# CH32F203C6T6-R0.net
KiCad netlist of a schematic drawn in Altium Designer
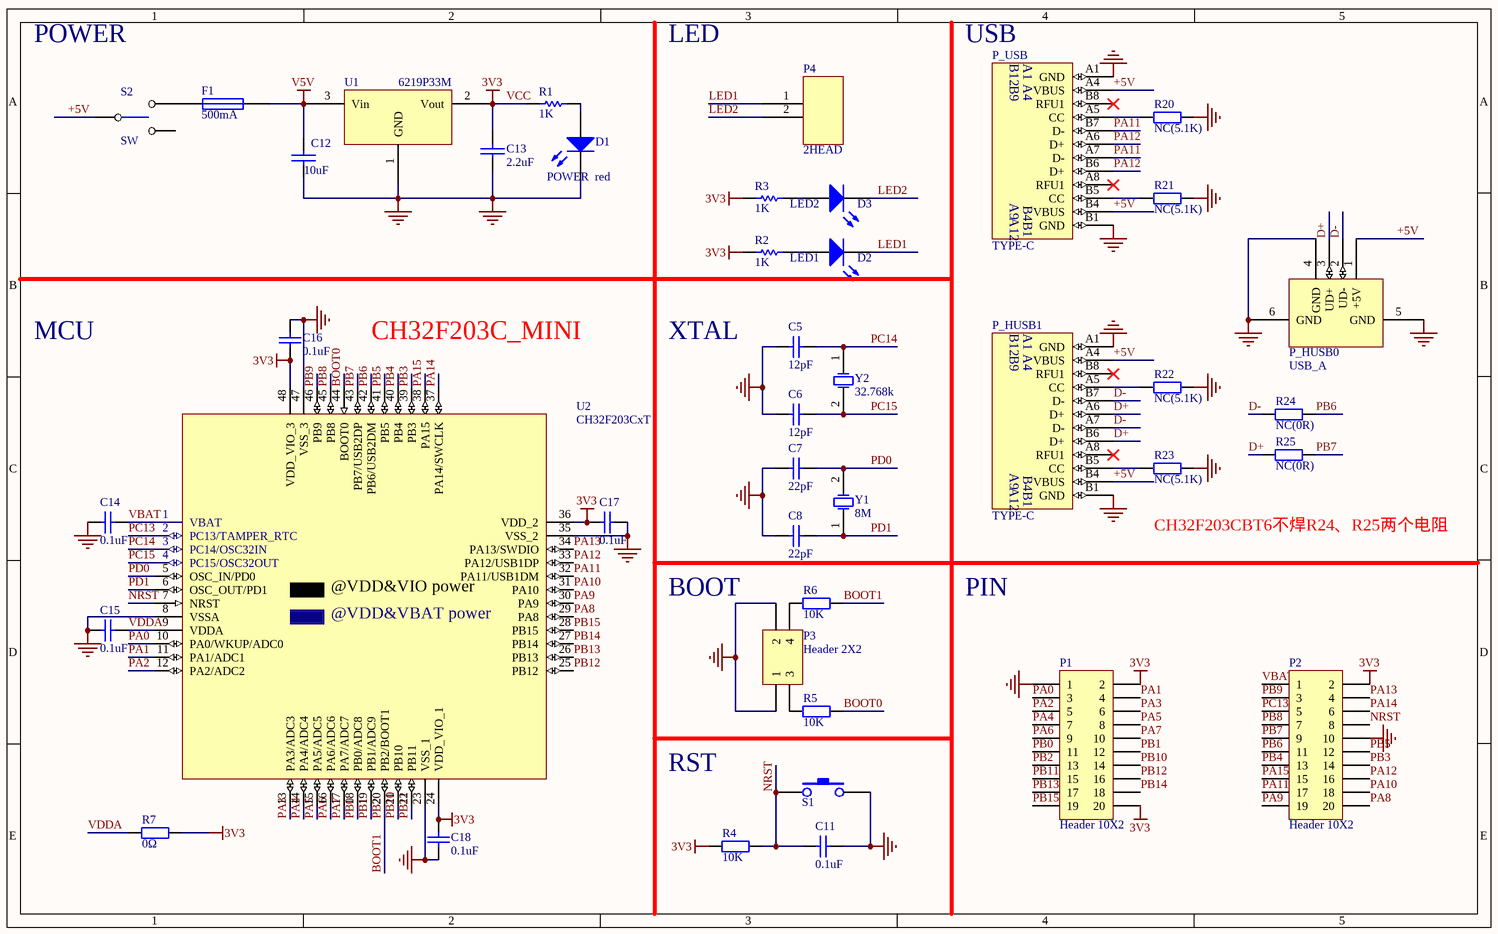
[diagram p0: CH32F203C6T6-R0.SchDoc]

(export (version "E")
  (design (tool "Eeschema 10.0.6"))
  (components
    (comp (ref "C5")
      (value "12pF")
      (footprint "0603")
      (description "Capacitor")
      (fields (field (name "PUBLISHER") "Altium Limited"))
      (libsource (lib "*") (part "Cap"))
    )
    (comp (ref "C6")
      (value "12pF")
      (footprint "0603")
      (description "Capacitor")
      (fields (field (name "PUBLISHER") "Altium Limited"))
      (libsource (lib "*") (part "Cap"))
    )
    (comp (ref "C7")
      (value "22pF")
      (footprint "0603")
      (description "Capacitor")
      (fields (field (name "PUBLISHER") "Altium Limited"))
      (libsource (lib "*") (part "Cap"))
    )
    (comp (ref "C8")
      (value "22pF")
      (footprint "0603")
      (description "Capacitor")
      (fields (field (name "PUBLISHER") "Altium Limited"))
      (libsource (lib "*") (part "Cap"))
    )
    (comp (ref "C11")
      (value "0.1uF")
      (footprint "0603")
      (description "Capacitor")
      (fields (field (name "PUBLISHER") "Altium Limited"))
      (libsource (lib "*") (part "Cap"))
    )
    (comp (ref "C12")
      (value "10uF")
      (footprint "3216")
      (description "Capacitor")
      (libsource (lib "*") (part "CAP"))
    )
    (comp (ref "C13")
      (value "2.2uF")
      (footprint "0603")
      (description "Capacitor")
      (libsource (lib "*") (part "CAP"))
    )
    (comp (ref "C14")
      (value "0.1uF")
      (footprint "0603")
      (description "Capacitor")
      (fields (field (name "PUBLISHER") "Altium Limited"))
      (libsource (lib "*") (part "Cap"))
    )
    (comp (ref "C15")
      (value "0.1uF")
      (footprint "0603")
      (description "Capacitor")
      (fields (field (name "PUBLISHER") "Altium Limited"))
      (libsource (lib "*") (part "Cap"))
    )
    (comp (ref "C16")
      (value "0.1uF")
      (footprint "0603")
      (description "Capacitor")
      (fields (field (name "PUBLISHER") "Altium Limited"))
      (libsource (lib "*") (part "Cap"))
    )
    (comp (ref "C17")
      (value "0.1uF")
      (footprint "0603")
      (description "Capacitor")
      (fields (field (name "PUBLISHER") "Altium Limited"))
      (libsource (lib "*") (part "Cap"))
    )
    (comp (ref "C18")
      (value "0.1uF")
      (footprint "0603")
      (description "Capacitor")
      (fields (field (name "PUBLISHER") "Altium Limited"))
      (libsource (lib "*") (part "Cap"))
    )
    (comp (ref "D1")
      (value "POWER  red")
      (footprint "0603L")
      (description "Typical INFRARED GaAs LED")
      (fields (field (name "PUBLISHER") "Altium Limited"))
      (libsource (lib "*") (part "LED0"))
    )
    (comp (ref "D2")
      (value "LED1")
      (footprint "0603L")
      (description "Typical INFRARED GaAs LED")
      (fields (field (name "PUBLISHER") "Altium Limited"))
      (libsource (lib "*") (part "LED0"))
    )
    (comp (ref "D3")
      (value "LED2")
      (footprint "0603L")
      (description "Typical INFRARED GaAs LED")
      (fields (field (name "PUBLISHER") "Altium Limited"))
      (libsource (lib "*") (part "LED0"))
    )
    (comp (ref "F1")
      (value "500mA")
      (footprint "0603")
      (description "Fuse")
      (libsource (lib "*") (part "FUSE1"))
    )
    (comp (ref "P1")
      (value "Header 10X2")
      (footprint "IDC20")
      (description "Header, 10-Pin, Dual row")
      (fields (field (name "PUBLISHER") "Altium Limited"))
      (libsource (lib "*") (part "Header 10X2"))
    )
    (comp (ref "P2")
      (value "Header 10X2")
      (footprint "IDC20")
      (description "Header, 10-Pin, Dual row")
      (fields (field (name "PUBLISHER") "Altium Limited"))
      (libsource (lib "*") (part "Header 10X2"))
    )
    (comp (ref "P3")
      (value "Header 2X2")
      (footprint "HDR2X2")
      (description "Header, 2-Pin, Dual row")
      (fields (field (name "PUBLISHER") "Altium Limited"))
      (libsource (lib "*") (part "Header 2X2"))
    )
    (comp (ref "P4") (value "2HEAD") (footprint "SIP2 - 40mil") (libsource (lib "*") (part "2HEAD")))
    (comp (ref "P_HUSB0")
      (value "USB_A")
      (footprint "USBA-L")
      (description "USB Port")
      (libsource (lib "*") (part "USB"))
    )
    (comp (ref "P_HUSB1")
      (value "TYPE-C")
      (footprint "TYPE-C-Receptacle-2.0")
      (libsource (lib "*") (part "TYPE-C1"))
    )
    (comp (ref "P_USB")
      (value "TYPE-C")
      (footprint "TYPE-C-Receptacle-2.0")
      (libsource (lib "*") (part "TYPE-C1"))
    )
    (comp (ref "R1")
      (value "1K")
      (footprint "0603")
      (description "Semiconductor Resistor")
      (fields (field (name "PUBLISHER") "Altium Limited"))
      (libsource (lib "*") (part "Res Semi"))
    )
    (comp (ref "R2")
      (value "1K")
      (footprint "0603")
      (description "Semiconductor Resistor")
      (fields (field (name "PUBLISHER") "Altium Limited"))
      (libsource (lib "*") (part "Res Semi"))
    )
    (comp (ref "R3")
      (value "1K")
      (footprint "0603")
      (description "Semiconductor Resistor")
      (fields (field (name "PUBLISHER") "Altium Limited"))
      (libsource (lib "*") (part "Res Semi"))
    )
    (comp (ref "R4")
      (value "10K")
      (footprint "0603")
      (description "Resistor")
      (fields (field (name "PUBLISHER") "Altium Limited"))
      (libsource (lib "*") (part "Res2"))
    )
    (comp (ref "R5")
      (value "10K")
      (footprint "0603")
      (description "Resistor")
      (fields (field (name "PUBLISHER") "Altium Limited"))
      (libsource (lib "*") (part "Res2"))
    )
    (comp (ref "R6")
      (value "10K")
      (footprint "0603")
      (description "Resistor")
      (fields (field (name "PUBLISHER") "Altium Limited"))
      (libsource (lib "*") (part "Res2"))
    )
    (comp (ref "R7")
      (value "0Ω")
      (footprint "0603")
      (description "Resistor")
      (fields (field (name "PUBLISHER") "Altium Limited"))
      (libsource (lib "*") (part "Res2"))
    )
    (comp (ref "R20")
      (value "NC(5.1K)")
      (footprint "0603")
      (description "Resistor")
      (libsource (lib "Miscellaneous Devices") (part "Res2"))
    )
    (comp (ref "R21")
      (value "NC(5.1K)")
      (footprint "0603")
      (description "Resistor")
      (libsource (lib "Miscellaneous Devices") (part "Res2"))
    )
    (comp (ref "R22")
      (value "NC(5.1K)")
      (footprint "0603")
      (description "Resistor")
      (libsource (lib "Miscellaneous Devices") (part "Res2"))
    )
    (comp (ref "R23")
      (value "NC(5.1K)")
      (footprint "0603")
      (description "Resistor")
      (libsource (lib "Miscellaneous Devices") (part "Res2"))
    )
    (comp (ref "R24")
      (value "NC(0R)")
      (footprint "0603")
      (description "Resistor")
      (libsource (lib "Miscellaneous Devices") (part "Res2"))
    )
    (comp (ref "R25")
      (value "NC(0R)")
      (footprint "0603")
      (description "Resistor")
      (libsource (lib "Miscellaneous Devices") (part "Res2"))
    )
    (comp (ref "S1") (value "KEY") (footprint "贴片按键") (libsource (lib "*") (part "KEY")))
    (comp (ref "S2") (value "SW") (footprint "KEY2") (libsource (lib "*") (part "SW")))
    (comp (ref "U1")
      (value "6219P33M")
      (footprint "SOT-23")
      (libsource (lib "wch_sch_others") (part "6219P33M"))
    )
    (comp (ref "U2")
      (value "CH32F203CxT")
      (footprint "LQFP48")
      (description "ARM M3 LMD-MCU, 144MHz, 2*USB FS, CAN")
      (libsource (lib "CHXXX") (part "CH32F203CxT"))
    )
    (comp (ref "Y1")
      (value "8M")
      (footprint "XT62/28")
      (description "Crystal Oscillator")
      (fields (field (name "PUBLISHER") "Altium Limited"))
      (libsource (lib "*") (part "XTAL"))
    )
    (comp (ref "Y2")
      (value "32.768k")
      (footprint "FC-135")
      (description "Crystal Oscillator")
      (fields (field (name "PUBLISHER") "Altium Limited"))
      (libsource (lib "*") (part "XTAL"))
    )
  )
  (nets
    (net (code "1") (name "/+5V") (class "Default")
      (node (ref "P_HUSB0") (pin "1") (pinfunction "+5V_1") (pintype "power_in"))
      (node (ref "P_HUSB1") (pin "A4") (pinfunction "VBUS_A4") (pintype "bidirectional"))
      (node (ref "P_HUSB1") (pin "B4") (pinfunction "VBUS_B4") (pintype "bidirectional"))
      (node (ref "P_USB") (pin "A4") (pinfunction "VBUS_A4") (pintype "bidirectional"))
      (node (ref "P_USB") (pin "B4") (pinfunction "VBUS_B4") (pintype "bidirectional"))
      (node (ref "S2") (pin "1") (pinfunction "1_1") (pintype "passive"))
    )
    (net (code "3") (name "/BOOT0") (class "Default")
      (node (ref "R5") (pin "1") (pinfunction "1_1") (pintype "passive"))
      (node (ref "U2") (pin "44") (pinfunction "BOOT0_44") (pintype "input"))
    )
    (net (code "4") (name "/BOOT1") (class "Default")
      (node (ref "P1") (pin "13") (pinfunction "13_13") (pintype "passive"))
      (node (ref "R6") (pin "1") (pinfunction "1_1") (pintype "passive"))
      (node (ref "U2") (pin "20") (pinfunction "PB2/BOOT1_20") (pintype "bidirectional"))
    )
    (net (code "5") (name "/D+") (class "Default")
      (node (ref "P_HUSB0") (pin "3") (pinfunction "UD+_3") (pintype "bidirectional"))
      (node (ref "P_HUSB1") (pin "A6") (pinfunction "D+_A6") (pintype "bidirectional"))
      (node (ref "P_HUSB1") (pin "B6") (pinfunction "D+_B6") (pintype "bidirectional"))
      (node (ref "R25") (pin "1") (pinfunction "1_1") (pintype "passive"))
    )
    (net (code "6") (name "/D-") (class "Default")
      (node (ref "P_HUSB0") (pin "2") (pinfunction "UD-_2") (pintype "bidirectional"))
      (node (ref "P_HUSB1") (pin "A7") (pinfunction "D-_A7") (pintype "bidirectional"))
      (node (ref "P_HUSB1") (pin "B7") (pinfunction "D-_B7") (pintype "bidirectional"))
      (node (ref "R24") (pin "1") (pinfunction "1_1") (pintype "passive"))
    )
    (net (code "7") (name "/LED1") (class "Default")
      (node (ref "D2") (pin "2") (pinfunction "K_2") (pintype "passive"))
      (node (ref "P4") (pin "1") (pintype "passive"))
    )
    (net (code "8") (name "/LED2") (class "Default")
      (node (ref "D3") (pin "2") (pinfunction "K_2") (pintype "passive"))
      (node (ref "P4") (pin "2") (pintype "passive"))
    )
    (net (code "9") (name "/NRST") (class "Default")
      (node (ref "C11") (pin "2") (pinfunction "2_2") (pintype "passive"))
      (node (ref "P2") (pin "8") (pinfunction "8_8") (pintype "passive"))
      (node (ref "R4") (pin "1") (pinfunction "1_1") (pintype "passive"))
      (node (ref "S1") (pin "1") (pinfunction "1_1") (pintype "passive"))
      (node (ref "U2") (pin "7") (pinfunction "NRST_7") (pintype "input"))
    )
    (net (code "10") (name "/PA0") (class "Default")
      (node (ref "P1") (pin "3") (pinfunction "3_3") (pintype "passive"))
      (node (ref "U2") (pin "10") (pinfunction "PA0/WKUP/ADC0_10") (pintype "bidirectional"))
    )
    (net (code "11") (name "/PA1") (class "Default")
      (node (ref "P1") (pin "4") (pinfunction "4_4") (pintype "passive"))
      (node (ref "U2") (pin "11") (pinfunction "PA1/ADC1_11") (pintype "bidirectional"))
    )
    (net (code "12") (name "/PA2") (class "Default")
      (node (ref "P1") (pin "5") (pinfunction "5_5") (pintype "passive"))
      (node (ref "U2") (pin "12") (pinfunction "PA2/ADC2_12") (pintype "bidirectional"))
    )
    (net (code "13") (name "/PA3") (class "Default")
      (node (ref "P1") (pin "6") (pinfunction "6_6") (pintype "passive"))
      (node (ref "U2") (pin "13") (pinfunction "PA3/ADC3_13") (pintype "bidirectional"))
    )
    (net (code "14") (name "/PA4") (class "Default")
      (node (ref "P1") (pin "7") (pinfunction "7_7") (pintype "passive"))
      (node (ref "U2") (pin "14") (pinfunction "PA4/ADC4_14") (pintype "bidirectional"))
    )
    (net (code "15") (name "/PA5") (class "Default")
      (node (ref "P1") (pin "8") (pinfunction "8_8") (pintype "passive"))
      (node (ref "U2") (pin "15") (pinfunction "PA5/ADC5_15") (pintype "bidirectional"))
    )
    (net (code "16") (name "/PA6") (class "Default")
      (node (ref "P1") (pin "9") (pinfunction "9_9") (pintype "passive"))
      (node (ref "U2") (pin "16") (pinfunction "PA6/ADC6_16") (pintype "bidirectional"))
    )
    (net (code "17") (name "/PA7") (class "Default")
      (node (ref "P1") (pin "10") (pinfunction "10_10") (pintype "passive"))
      (node (ref "U2") (pin "17") (pinfunction "PA7/ADC7_17") (pintype "bidirectional"))
    )
    (net (code "18") (name "/PA8") (class "Default")
      (node (ref "P2") (pin "20") (pinfunction "20_20") (pintype "passive"))
      (node (ref "U2") (pin "29") (pinfunction "PA8_29") (pintype "bidirectional"))
    )
    (net (code "19") (name "/PA9") (class "Default")
      (node (ref "P2") (pin "19") (pinfunction "19_19") (pintype "passive"))
      (node (ref "U2") (pin "30") (pinfunction "PA9_30") (pintype "bidirectional"))
    )
    (net (code "20") (name "/PA10") (class "Default")
      (node (ref "P2") (pin "18") (pinfunction "18_18") (pintype "passive"))
      (node (ref "U2") (pin "31") (pinfunction "PA10_31") (pintype "bidirectional"))
    )
    (net (code "21") (name "/PA11") (class "Default")
      (node (ref "P2") (pin "17") (pinfunction "17_17") (pintype "passive"))
      (node (ref "P_USB") (pin "A7") (pinfunction "D-_A7") (pintype "bidirectional"))
      (node (ref "P_USB") (pin "B7") (pinfunction "D-_B7") (pintype "bidirectional"))
      (node (ref "U2") (pin "32") (pinfunction "PA11/USB1DM_32") (pintype "bidirectional"))
    )
    (net (code "22") (name "/PA12") (class "Default")
      (node (ref "P2") (pin "16") (pinfunction "16_16") (pintype "passive"))
      (node (ref "P_USB") (pin "A6") (pinfunction "D+_A6") (pintype "bidirectional"))
      (node (ref "P_USB") (pin "B6") (pinfunction "D+_B6") (pintype "bidirectional"))
      (node (ref "U2") (pin "33") (pinfunction "PA12/USB1DP_33") (pintype "bidirectional"))
    )
    (net (code "23") (name "/PA13") (class "Default")
      (node (ref "P2") (pin "4") (pinfunction "4_4") (pintype "passive"))
      (node (ref "U2") (pin "34") (pinfunction "PA13/SWDIO_34") (pintype "bidirectional"))
    )
    (net (code "24") (name "/PA14") (class "Default")
      (node (ref "P2") (pin "6") (pinfunction "6_6") (pintype "passive"))
      (node (ref "U2") (pin "37") (pinfunction "PA14/SWCLK_37") (pintype "bidirectional"))
    )
    (net (code "25") (name "/PA15") (class "Default")
      (node (ref "P2") (pin "15") (pinfunction "15_15") (pintype "passive"))
      (node (ref "U2") (pin "38") (pinfunction "PA15_38") (pintype "bidirectional"))
    )
    (net (code "26") (name "/PB0") (class "Default")
      (node (ref "P1") (pin "11") (pinfunction "11_11") (pintype "passive"))
      (node (ref "U2") (pin "18") (pinfunction "PB0/ADC8_18") (pintype "bidirectional"))
    )
    (net (code "27") (name "/PB1") (class "Default")
      (node (ref "P1") (pin "12") (pinfunction "12_12") (pintype "passive"))
      (node (ref "U2") (pin "19") (pinfunction "PB1/ADC9_19") (pintype "bidirectional"))
    )
    (net (code "28") (name "/PB3") (class "Default")
      (node (ref "P2") (pin "14") (pinfunction "14_14") (pintype "passive"))
      (node (ref "U2") (pin "39") (pinfunction "PB3_39") (pintype "bidirectional"))
    )
    (net (code "29") (name "/PB4") (class "Default")
      (node (ref "P2") (pin "13") (pinfunction "13_13") (pintype "passive"))
      (node (ref "U2") (pin "40") (pinfunction "PB4_40") (pintype "bidirectional"))
    )
    (net (code "30") (name "/PB5") (class "Default")
      (node (ref "P2") (pin "12") (pinfunction "12_12") (pintype "passive"))
      (node (ref "U2") (pin "41") (pinfunction "PB5_41") (pintype "bidirectional"))
    )
    (net (code "31") (name "/PB6") (class "Default")
      (node (ref "P2") (pin "11") (pinfunction "11_11") (pintype "passive"))
      (node (ref "R24") (pin "2") (pinfunction "2_2") (pintype "passive"))
      (node (ref "U2") (pin "42") (pinfunction "PB6/USB2DM_42") (pintype "bidirectional"))
    )
    (net (code "32") (name "/PB7") (class "Default")
      (node (ref "P2") (pin "9") (pinfunction "9_9") (pintype "passive"))
      (node (ref "R25") (pin "2") (pinfunction "2_2") (pintype "passive"))
      (node (ref "U2") (pin "43") (pinfunction "PB7/USB2DP_43") (pintype "bidirectional"))
    )
    (net (code "33") (name "/PB8") (class "Default")
      (node (ref "P2") (pin "7") (pinfunction "7_7") (pintype "passive"))
      (node (ref "U2") (pin "45") (pinfunction "PB8_45") (pintype "bidirectional"))
    )
    (net (code "34") (name "/PB9") (class "Default")
      (node (ref "P2") (pin "3") (pinfunction "3_3") (pintype "passive"))
      (node (ref "U2") (pin "46") (pinfunction "PB9_46") (pintype "bidirectional"))
    )
    (net (code "35") (name "/PB10") (class "Default")
      (node (ref "P1") (pin "14") (pinfunction "14_14") (pintype "passive"))
      (node (ref "U2") (pin "21") (pinfunction "PB10_21") (pintype "bidirectional"))
    )
    (net (code "36") (name "/PB11") (class "Default")
      (node (ref "P1") (pin "15") (pinfunction "15_15") (pintype "passive"))
      (node (ref "U2") (pin "22") (pinfunction "PB11_22") (pintype "bidirectional"))
    )
    (net (code "37") (name "/PB12") (class "Default")
      (node (ref "P1") (pin "16") (pinfunction "16_16") (pintype "passive"))
      (node (ref "U2") (pin "25") (pinfunction "PB12_25") (pintype "bidirectional"))
    )
    (net (code "38") (name "/PB13") (class "Default")
      (node (ref "P1") (pin "17") (pinfunction "17_17") (pintype "passive"))
      (node (ref "U2") (pin "26") (pinfunction "PB13_26") (pintype "bidirectional"))
    )
    (net (code "39") (name "/PB14") (class "Default")
      (node (ref "P1") (pin "18") (pinfunction "18_18") (pintype "passive"))
      (node (ref "U2") (pin "27") (pinfunction "PB14_27") (pintype "bidirectional"))
    )
    (net (code "40") (name "/PB15") (class "Default")
      (node (ref "P1") (pin "19") (pinfunction "19_19") (pintype "passive"))
      (node (ref "U2") (pin "28") (pinfunction "PB15_28") (pintype "bidirectional"))
    )
    (net (code "41") (name "/PC13") (class "Default")
      (node (ref "P2") (pin "5") (pinfunction "5_5") (pintype "passive"))
      (node (ref "U2") (pin "2") (pinfunction "PC13/TAMPER_RTC_2") (pintype "bidirectional"))
    )
    (net (code "42") (name "/PC14") (class "Default")
      (node (ref "C5") (pin "1") (pinfunction "1_1") (pintype "passive"))
      (node (ref "U2") (pin "3") (pinfunction "PC14/OSC32IN_3") (pintype "bidirectional"))
      (node (ref "Y2") (pin "1") (pinfunction "OSC1_1") (pintype "passive"))
    )
    (net (code "43") (name "/PC15") (class "Default")
      (node (ref "C6") (pin "1") (pinfunction "1_1") (pintype "passive"))
      (node (ref "U2") (pin "4") (pinfunction "PC15/OSC32OUT_4") (pintype "bidirectional"))
      (node (ref "Y2") (pin "2") (pinfunction "OSC2_2") (pintype "passive"))
    )
    (net (code "44") (name "/PD0") (class "Default")
      (node (ref "C7") (pin "2") (pinfunction "2_2") (pintype "passive"))
      (node (ref "U2") (pin "5") (pinfunction "OSC_IN/PD0_5") (pintype "bidirectional"))
      (node (ref "Y1") (pin "2") (pinfunction "OSC2_2") (pintype "passive"))
    )
    (net (code "45") (name "/PD1") (class "Default")
      (node (ref "C8") (pin "2") (pinfunction "2_2") (pintype "passive"))
      (node (ref "U2") (pin "6") (pinfunction "OSC_OUT/PD1_6") (pintype "bidirectional"))
      (node (ref "Y1") (pin "1") (pinfunction "OSC1_1") (pintype "passive"))
    )
    (net (code "46") (name "/VBAT") (class "Default")
      (node (ref "C14") (pin "1") (pinfunction "1_1") (pintype "passive"))
      (node (ref "P2") (pin "1") (pinfunction "1_1") (pintype "passive"))
      (node (ref "U2") (pin "1") (pinfunction "VBAT_1") (pintype "power_in"))
    )
    (net (code "47") (name "/VDDA") (class "Default")
      (node (ref "C15") (pin "1") (pinfunction "1_1") (pintype "passive"))
      (node (ref "R7") (pin "2") (pinfunction "2_2") (pintype "passive"))
      (node (ref "U2") (pin "9") (pinfunction "VDDA_9") (pintype "power_in"))
    )
    (net (code "48") (name "3V3") (class "Default")
      (node (ref "C13") (pin "1") (pinfunction "1_1") (pintype "passive"))
      (node (ref "C16") (pin "2") (pinfunction "2_2") (pintype "passive"))
      (node (ref "C17") (pin "2") (pinfunction "2_2") (pintype "passive"))
      (node (ref "C18") (pin "2") (pinfunction "2_2") (pintype "passive"))
      (node (ref "P1") (pin "2") (pinfunction "2_2") (pintype "passive"))
      (node (ref "P1") (pin "20") (pinfunction "20_20") (pintype "passive"))
      (node (ref "P2") (pin "2") (pinfunction "2_2") (pintype "passive"))
      (node (ref "R1") (pin "2") (pinfunction "2_2") (pintype "passive"))
      (node (ref "R2") (pin "1") (pinfunction "1_1") (pintype "passive"))
      (node (ref "R3") (pin "1") (pinfunction "1_1") (pintype "passive"))
      (node (ref "R4") (pin "2") (pinfunction "2_2") (pintype "passive"))
      (node (ref "R7") (pin "1") (pinfunction "1_1") (pintype "passive"))
      (node (ref "U1") (pin "2") (pinfunction "Vout_2") (pintype "passive"))
      (node (ref "U2") (pin "24") (pinfunction "VDD_VIO_1_24") (pintype "power_in"))
      (node (ref "U2") (pin "36") (pinfunction "VDD_2_36") (pintype "power_in"))
      (node (ref "U2") (pin "48") (pinfunction "VDD_VIO_3_48") (pintype "power_in"))
    )
    (net (code "49") (name "GND") (class "Default")
      (node (ref "C11") (pin "1") (pinfunction "1_1") (pintype "passive"))
      (node (ref "C12") (pin "2") (pinfunction "2_2") (pintype "passive"))
      (node (ref "C13") (pin "2") (pinfunction "2_2") (pintype "passive"))
      (node (ref "C14") (pin "2") (pinfunction "2_2") (pintype "passive"))
      (node (ref "C15") (pin "2") (pinfunction "2_2") (pintype "passive"))
      (node (ref "C16") (pin "1") (pinfunction "1_1") (pintype "passive"))
      (node (ref "C17") (pin "1") (pinfunction "1_1") (pintype "passive"))
      (node (ref "C18") (pin "1") (pinfunction "1_1") (pintype "passive"))
      (node (ref "C5") (pin "2") (pinfunction "2_2") (pintype "passive"))
      (node (ref "C6") (pin "2") (pinfunction "2_2") (pintype "passive"))
      (node (ref "C7") (pin "1") (pinfunction "1_1") (pintype "passive"))
      (node (ref "C8") (pin "1") (pinfunction "1_1") (pintype "passive"))
      (node (ref "D1") (pin "2") (pinfunction "K_2") (pintype "passive"))
      (node (ref "P1") (pin "1") (pinfunction "1_1") (pintype "passive"))
      (node (ref "P2") (pin "10") (pinfunction "10_10") (pintype "passive"))
      (node (ref "P3") (pin "1") (pinfunction "1_1") (pintype "passive"))
      (node (ref "P3") (pin "2") (pinfunction "2_2") (pintype "passive"))
      (node (ref "P_HUSB0") (pin "4") (pinfunction "GND_4") (pintype "power_in"))
      (node (ref "P_HUSB0") (pin "5") (pinfunction "GND_5") (pintype "power_in"))
      (node (ref "P_HUSB0") (pin "6") (pinfunction "GND_6") (pintype "power_in"))
      (node (ref "P_HUSB1") (pin "A1") (pinfunction "GND_A1") (pintype "bidirectional"))
      (node (ref "P_HUSB1") (pin "B1") (pinfunction "GND_B1") (pintype "bidirectional"))
      (node (ref "P_USB") (pin "A1") (pinfunction "GND_A1") (pintype "bidirectional"))
      (node (ref "P_USB") (pin "B1") (pinfunction "GND_B1") (pintype "bidirectional"))
      (node (ref "R20") (pin "2") (pinfunction "2_2") (pintype "passive"))
      (node (ref "R21") (pin "2") (pinfunction "2_2") (pintype "passive"))
      (node (ref "R22") (pin "2") (pinfunction "2_2") (pintype "passive"))
      (node (ref "R23") (pin "2") (pinfunction "2_2") (pintype "passive"))
      (node (ref "S1") (pin "3") (pinfunction "3_3") (pintype "passive"))
      (node (ref "U1") (pin "1") (pinfunction "GND_1") (pintype "passive"))
      (node (ref "U2") (pin "23") (pinfunction "VSS_1_23") (pintype "power_in"))
      (node (ref "U2") (pin "35") (pinfunction "VSS_2_35") (pintype "power_in"))
      (node (ref "U2") (pin "47") (pinfunction "VSS_3_47") (pintype "power_in"))
      (node (ref "U2") (pin "8") (pinfunction "VSSA_8") (pintype "power_in"))
    )
    (net (code "50") (name "Net-(D1-A)") (class "Default")
      (node (ref "D1") (pin "1") (pinfunction "A_1") (pintype "passive"))
      (node (ref "R1") (pin "1") (pinfunction "1_1") (pintype "passive"))
    )
    (net (code "51") (name "Net-(D2-A)") (class "Default")
      (node (ref "D2") (pin "1") (pinfunction "A_1") (pintype "passive"))
      (node (ref "R2") (pin "2") (pinfunction "2_2") (pintype "passive"))
    )
    (net (code "52") (name "Net-(D3-A)") (class "Default")
      (node (ref "D3") (pin "1") (pinfunction "A_1") (pintype "passive"))
      (node (ref "R3") (pin "2") (pinfunction "2_2") (pintype "passive"))
    )
    (net (code "53") (name "Net-(F1-Pad1)") (class "Default")
      (node (ref "F1") (pin "1") (pinfunction "1_1") (pintype "passive"))
      (node (ref "S2") (pin "3") (pinfunction "3_3") (pintype "passive"))
    )
    (net (code "54") (name "Net-(P3-Pad3)") (class "Default")
      (node (ref "P3") (pin "3") (pinfunction "3_3") (pintype "passive"))
      (node (ref "R5") (pin "2") (pinfunction "2_2") (pintype "passive"))
    )
    (net (code "55") (name "Net-(P3-Pad4)") (class "Default")
      (node (ref "P3") (pin "4") (pinfunction "4_4") (pintype "passive"))
      (node (ref "R6") (pin "2") (pinfunction "2_2") (pintype "passive"))
    )
    (net (code "56") (name "Net-(P_HUSB1-CC-PadA5)") (class "Default")
      (node (ref "P_HUSB1") (pin "A5") (pinfunction "CC_A5") (pintype "bidirectional"))
      (node (ref "R22") (pin "1") (pinfunction "1_1") (pintype "passive"))
    )
    (net (code "57") (name "Net-(P_HUSB1-CC-PadB5)") (class "Default")
      (node (ref "P_HUSB1") (pin "B5") (pinfunction "CC_B5") (pintype "bidirectional"))
      (node (ref "R23") (pin "1") (pinfunction "1_1") (pintype "passive"))
    )
    (net (code "58") (name "Net-(P_USB-CC-PadA5)") (class "Default")
      (node (ref "P_USB") (pin "A5") (pinfunction "CC_A5") (pintype "bidirectional"))
      (node (ref "R20") (pin "1") (pinfunction "1_1") (pintype "passive"))
    )
    (net (code "59") (name "Net-(P_USB-CC-PadB5)") (class "Default")
      (node (ref "P_USB") (pin "B5") (pinfunction "CC_B5") (pintype "bidirectional"))
      (node (ref "R21") (pin "1") (pinfunction "1_1") (pintype "passive"))
    )
    (net (code "60") (name "V5V") (class "Default")
      (node (ref "C12") (pin "1") (pinfunction "1_1") (pintype "passive"))
      (node (ref "F1") (pin "2") (pinfunction "2_2") (pintype "passive"))
      (node (ref "U1") (pin "3") (pinfunction "Vin_3") (pintype "passive"))
    )
    (net (code "61") (name "unconnected-(P_HUSB1-RFU1-PadA8)") (class "Default")
      (node (ref "P_HUSB1") (pin "A8") (pinfunction "RFU1_A8") (pintype "bidirectional+no_connect"))
    )
    (net (code "62") (name "unconnected-(P_HUSB1-RFU1-PadB8)") (class "Default")
      (node (ref "P_HUSB1") (pin "B8") (pinfunction "RFU1_B8") (pintype "bidirectional+no_connect"))
    )
    (net (code "63") (name "unconnected-(P_USB-RFU1-PadA8)") (class "Default")
      (node (ref "P_USB") (pin "A8") (pinfunction "RFU1_A8") (pintype "bidirectional+no_connect"))
    )
    (net (code "64") (name "unconnected-(P_USB-RFU1-PadB8)") (class "Default")
      (node (ref "P_USB") (pin "B8") (pinfunction "RFU1_B8") (pintype "bidirectional+no_connect"))
    )
    (net (code "65") (name "unconnected-(S2-Pad2)") (class "Default")
      (node (ref "S2") (pin "2") (pinfunction "2_2") (pintype "passive"))
    )
  )
)
